# CPU-0.net
KiCad netlist of a schematic drawn in Altium Designer
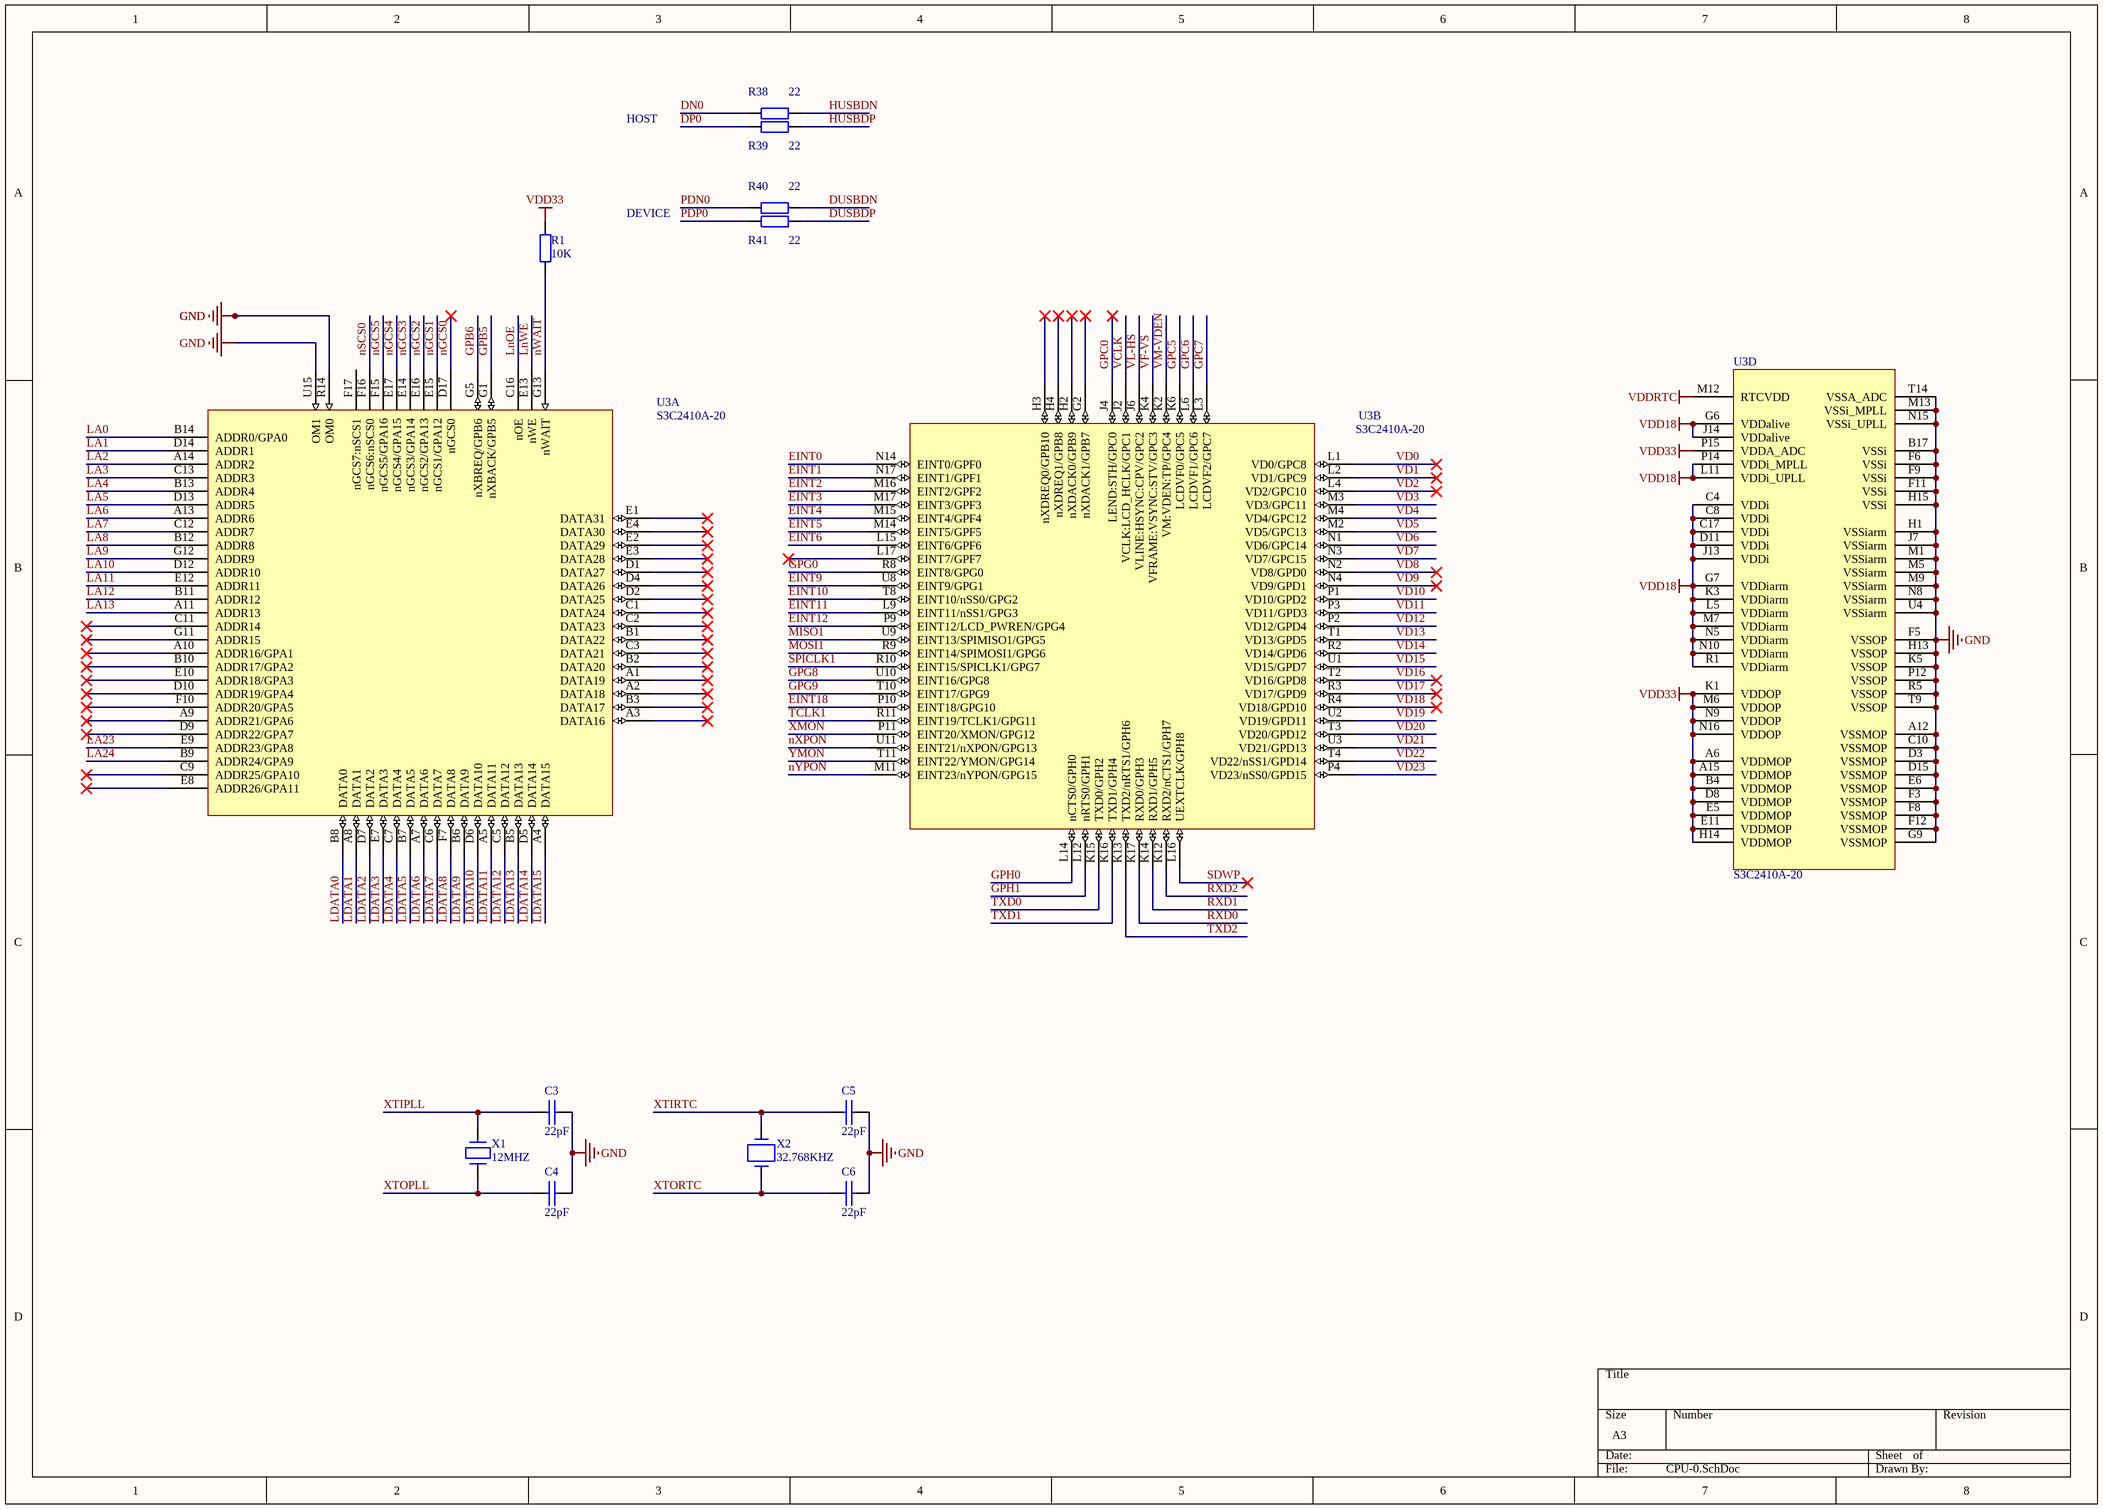
[diagram p0: CPU-0.SchDoc]

(export (version "E")
  (design (tool "Eeschema 10.0.6"))
  (components
    (comp (ref "C3")
      (value "22pF")
      (footprint "A型钽电容")
      (description "Capacitor")
      (libsource (lib "ARM_DEMO") (part "CAP_1"))
    )
    (comp (ref "C4")
      (value "22pF")
      (footprint "A型钽电容")
      (description "Capacitor")
      (libsource (lib "ARM_DEMO") (part "CAP_1"))
    )
    (comp (ref "C5")
      (value "22pF")
      (footprint "A型钽电容")
      (description "Capacitor")
      (libsource (lib "ARM_DEMO") (part "CAP_1"))
    )
    (comp (ref "C6")
      (value "22pF")
      (footprint "A型钽电容")
      (description "Capacitor")
      (libsource (lib "ARM_DEMO") (part "CAP_1"))
    )
    (comp (ref "R1")
      (value "10K")
      (footprint "0603R")
      (description "Resistor")
      (fields (field (name "Comment") "Res2") (field (name "PUBLISHER") "Altium Limited"))
      (libsource (lib "") (part "Res2_1_1"))
    )
    (comp (ref "R38")
      (value "22")
      (footprint "0603R")
      (description "Resistor")
      (fields (field (name "Comment") "Res2") (field (name "PUBLISHER") "Altium Limited"))
      (libsource (lib "ARM_DEMO") (part "Res2_1"))
    )
    (comp (ref "R39")
      (value "22")
      (footprint "0603R")
      (description "Resistor")
      (fields (field (name "Comment") "Res2") (field (name "PUBLISHER") "Altium Limited"))
      (libsource (lib "ARM_DEMO") (part "Res2_1"))
    )
    (comp (ref "R40")
      (value "22")
      (footprint "0603R")
      (description "Resistor")
      (fields (field (name "Comment") "Res2") (field (name "PUBLISHER") "Altium Limited"))
      (libsource (lib "ARM_DEMO") (part "Res2_1"))
    )
    (comp (ref "R41")
      (value "22")
      (footprint "0603R")
      (description "Resistor")
      (fields (field (name "Comment") "Res2") (field (name "PUBLISHER") "Altium Limited"))
      (libsource (lib "ARM_DEMO") (part "Res2_1"))
    )
    (comp (ref "U3")
      (value "S3C2410A-20")
      (footprint "FBGA272")
      (description "32-Bit RISC Microprocessor, 200 MHz, 1.8V (Core), 3.3V (Memory and IO), 272-Pin FBGA")
      (fields (field (name "PUBLISHER") "Altium Limited"))
      (libsource (lib "ARM_DEMO") (part "S3C2410A-20"))
    )
    (comp (ref "X1") (value "12MHZ") (footprint "OSC2PR-1") (libsource (lib "ARM_DEMO") (part "CRYSTAL")))
    (comp (ref "X2") (value "32.768KHZ") (footprint "XTAL-B") (libsource (lib "ARM_DEMO") (part "CRYSTAL_1")))
  )
  (nets
    (net (code "1") (name "/DN0") (class "Default")
      (node (ref "R38") (pin "1") (pinfunction "1_1") (pintype "passive"))
    )
    (net (code "2") (name "/DP0") (class "Default")
      (node (ref "R39") (pin "1") (pinfunction "1_1") (pintype "passive"))
    )
    (net (code "3") (name "/DUSBDN") (class "Default")
      (node (ref "R40") (pin "2") (pinfunction "2_2") (pintype "passive"))
    )
    (net (code "4") (name "/DUSBDP") (class "Default")
      (node (ref "R41") (pin "2") (pinfunction "2_2") (pintype "passive"))
    )
    (net (code "5") (name "/EINT0") (class "Default")
      (node (ref "U3") (pin "N14") (pinfunction "EINT0/GPF0_N14") (pintype "bidirectional"))
    )
    (net (code "6") (name "/EINT1") (class "Default")
      (node (ref "U3") (pin "N17") (pinfunction "EINT1/GPF1_N17") (pintype "bidirectional"))
    )
    (net (code "7") (name "/EINT2") (class "Default")
      (node (ref "U3") (pin "M16") (pinfunction "EINT2/GPF2_M16") (pintype "bidirectional"))
    )
    (net (code "8") (name "/EINT3") (class "Default")
      (node (ref "U3") (pin "M17") (pinfunction "EINT3/GPF3_M17") (pintype "bidirectional"))
    )
    (net (code "9") (name "/EINT4") (class "Default")
      (node (ref "U3") (pin "M15") (pinfunction "EINT4/GPF4_M15") (pintype "bidirectional"))
    )
    (net (code "10") (name "/EINT5") (class "Default")
      (node (ref "U3") (pin "M14") (pinfunction "EINT5/GPF5_M14") (pintype "bidirectional"))
    )
    (net (code "11") (name "/EINT6") (class "Default")
      (node (ref "U3") (pin "L15") (pinfunction "EINT6/GPF6_L15") (pintype "bidirectional"))
    )
    (net (code "12") (name "/EINT9") (class "Default")
      (node (ref "U3") (pin "U8") (pinfunction "EINT9/GPG1_U8") (pintype "bidirectional"))
    )
    (net (code "13") (name "/EINT10") (class "Default")
      (node (ref "U3") (pin "T8") (pinfunction "EINT10/nSS0/GPG2_T8") (pintype "bidirectional"))
    )
    (net (code "14") (name "/EINT11") (class "Default")
      (node (ref "U3") (pin "L9") (pinfunction "EINT11/nSS1/GPG3_L9") (pintype "bidirectional"))
    )
    (net (code "15") (name "/EINT12") (class "Default")
      (node (ref "U3") (pin "P9") (pinfunction "EINT12/LCD_PWREN/GPG4_P9") (pintype "bidirectional"))
    )
    (net (code "16") (name "/EINT18") (class "Default")
      (node (ref "U3") (pin "P10") (pinfunction "EINT18/GPG10_P10") (pintype "bidirectional"))
    )
    (net (code "17") (name "/GPB5") (class "Default")
      (node (ref "U3") (pin "G1") (pinfunction "nXBACK/GPB5_G1") (pintype "bidirectional"))
    )
    (net (code "18") (name "/GPB6") (class "Default")
      (node (ref "U3") (pin "G5") (pinfunction "nXBREQ/GPB6_G5") (pintype "bidirectional"))
    )
    (net (code "19") (name "/GPC0") (class "Default")
      (node (ref "U3") (pin "J4") (pinfunction "LEND:STH/GPC0_J4") (pintype "bidirectional+no_connect"))
    )
    (net (code "20") (name "/GPC5") (class "Default")
      (node (ref "U3") (pin "K6") (pinfunction "LCDVF0/GPC5_K6") (pintype "bidirectional"))
    )
    (net (code "21") (name "/GPC6") (class "Default")
      (node (ref "U3") (pin "L6") (pinfunction "LCDVF1/GPC6_L6") (pintype "bidirectional"))
    )
    (net (code "22") (name "/GPC7") (class "Default")
      (node (ref "U3") (pin "L3") (pinfunction "LCDVF2/GPC7_L3") (pintype "bidirectional"))
    )
    (net (code "23") (name "/GPG0") (class "Default")
      (node (ref "U3") (pin "R8") (pinfunction "EINT8/GPG0_R8") (pintype "bidirectional"))
    )
    (net (code "24") (name "/GPG8") (class "Default")
      (node (ref "U3") (pin "U10") (pinfunction "EINT16/GPG8_U10") (pintype "bidirectional"))
    )
    (net (code "25") (name "/GPG9") (class "Default")
      (node (ref "U3") (pin "T10") (pinfunction "EINT17/GPG9_T10") (pintype "bidirectional"))
    )
    (net (code "26") (name "/GPH0") (class "Default")
      (node (ref "U3") (pin "L14") (pinfunction "nCTS0/GPH0_L14") (pintype "bidirectional"))
    )
    (net (code "27") (name "/GPH1") (class "Default")
      (node (ref "U3") (pin "L12") (pinfunction "nRTS0/GPH1_L12") (pintype "bidirectional"))
    )
    (net (code "28") (name "/HUSBDN") (class "Default")
      (node (ref "R38") (pin "2") (pinfunction "2_2") (pintype "passive"))
    )
    (net (code "29") (name "/HUSBDP") (class "Default")
      (node (ref "R39") (pin "2") (pinfunction "2_2") (pintype "passive"))
    )
    (net (code "30") (name "/LA0") (class "Default")
      (node (ref "U3") (pin "B14") (pinfunction "ADDR0/GPA0_B14") (pintype "tri_state"))
    )
    (net (code "31") (name "/LA1") (class "Default")
      (node (ref "U3") (pin "D14") (pinfunction "ADDR1_D14") (pintype "tri_state"))
    )
    (net (code "32") (name "/LA2") (class "Default")
      (node (ref "U3") (pin "A14") (pinfunction "ADDR2_A14") (pintype "tri_state"))
    )
    (net (code "33") (name "/LA3") (class "Default")
      (node (ref "U3") (pin "C13") (pinfunction "ADDR3_C13") (pintype "tri_state"))
    )
    (net (code "34") (name "/LA4") (class "Default")
      (node (ref "U3") (pin "B13") (pinfunction "ADDR4_B13") (pintype "tri_state"))
    )
    (net (code "35") (name "/LA5") (class "Default")
      (node (ref "U3") (pin "D13") (pinfunction "ADDR5_D13") (pintype "tri_state"))
    )
    (net (code "36") (name "/LA6") (class "Default")
      (node (ref "U3") (pin "A13") (pinfunction "ADDR6_A13") (pintype "tri_state"))
    )
    (net (code "37") (name "/LA7") (class "Default")
      (node (ref "U3") (pin "C12") (pinfunction "ADDR7_C12") (pintype "tri_state"))
    )
    (net (code "38") (name "/LA8") (class "Default")
      (node (ref "U3") (pin "B12") (pinfunction "ADDR8_B12") (pintype "tri_state"))
    )
    (net (code "39") (name "/LA9") (class "Default")
      (node (ref "U3") (pin "G12") (pinfunction "ADDR9_G12") (pintype "tri_state"))
    )
    (net (code "40") (name "/LA10") (class "Default")
      (node (ref "U3") (pin "D12") (pinfunction "ADDR10_D12") (pintype "tri_state"))
    )
    (net (code "41") (name "/LA11") (class "Default")
      (node (ref "U3") (pin "E12") (pinfunction "ADDR11_E12") (pintype "tri_state"))
    )
    (net (code "42") (name "/LA12") (class "Default")
      (node (ref "U3") (pin "B11") (pinfunction "ADDR12_B11") (pintype "tri_state"))
    )
    (net (code "43") (name "/LA13") (class "Default")
      (node (ref "U3") (pin "A11") (pinfunction "ADDR13_A11") (pintype "tri_state"))
    )
    (net (code "44") (name "/LA23") (class "Default")
      (node (ref "U3") (pin "E9") (pinfunction "ADDR23/GPA8_E9") (pintype "tri_state"))
    )
    (net (code "45") (name "/LA24") (class "Default")
      (node (ref "U3") (pin "B9") (pinfunction "ADDR24/GPA9_B9") (pintype "tri_state"))
    )
    (net (code "46") (name "/LDATA0") (class "Default")
      (node (ref "U3") (pin "B8") (pinfunction "DATA0_B8") (pintype "bidirectional"))
    )
    (net (code "47") (name "/LDATA1") (class "Default")
      (node (ref "U3") (pin "A8") (pinfunction "DATA1_A8") (pintype "bidirectional"))
    )
    (net (code "48") (name "/LDATA2") (class "Default")
      (node (ref "U3") (pin "D7") (pinfunction "DATA2_D7") (pintype "bidirectional"))
    )
    (net (code "49") (name "/LDATA3") (class "Default")
      (node (ref "U3") (pin "E7") (pinfunction "DATA3_E7") (pintype "bidirectional"))
    )
    (net (code "50") (name "/LDATA4") (class "Default")
      (node (ref "U3") (pin "C7") (pinfunction "DATA4_C7") (pintype "bidirectional"))
    )
    (net (code "51") (name "/LDATA5") (class "Default")
      (node (ref "U3") (pin "B7") (pinfunction "DATA5_B7") (pintype "bidirectional"))
    )
    (net (code "52") (name "/LDATA6") (class "Default")
      (node (ref "U3") (pin "A7") (pinfunction "DATA6_A7") (pintype "bidirectional"))
    )
    (net (code "53") (name "/LDATA7") (class "Default")
      (node (ref "U3") (pin "C6") (pinfunction "DATA7_C6") (pintype "bidirectional"))
    )
    (net (code "54") (name "/LDATA8") (class "Default")
      (node (ref "U3") (pin "F7") (pinfunction "DATA8_F7") (pintype "bidirectional"))
    )
    (net (code "55") (name "/LDATA9") (class "Default")
      (node (ref "U3") (pin "B6") (pinfunction "DATA9_B6") (pintype "bidirectional"))
    )
    (net (code "56") (name "/LDATA10") (class "Default")
      (node (ref "U3") (pin "D6") (pinfunction "DATA10_D6") (pintype "bidirectional"))
    )
    (net (code "57") (name "/LDATA11") (class "Default")
      (node (ref "U3") (pin "A5") (pinfunction "DATA11_A5") (pintype "bidirectional"))
    )
    (net (code "58") (name "/LDATA12") (class "Default")
      (node (ref "U3") (pin "C5") (pinfunction "DATA12_C5") (pintype "bidirectional"))
    )
    (net (code "59") (name "/LDATA13") (class "Default")
      (node (ref "U3") (pin "B5") (pinfunction "DATA13_B5") (pintype "bidirectional"))
    )
    (net (code "60") (name "/LDATA14") (class "Default")
      (node (ref "U3") (pin "D5") (pinfunction "DATA14_D5") (pintype "bidirectional"))
    )
    (net (code "61") (name "/LDATA15") (class "Default")
      (node (ref "U3") (pin "A4") (pinfunction "DATA15_A4") (pintype "bidirectional"))
    )
    (net (code "62") (name "/LnOE") (class "Default")
      (node (ref "U3") (pin "C16") (pinfunction "nOE_C16") (pintype "tri_state"))
    )
    (net (code "63") (name "/LnWE") (class "Default")
      (node (ref "U3") (pin "E13") (pinfunction "nWE_E13") (pintype "tri_state"))
    )
    (net (code "64") (name "/MISO1") (class "Default")
      (node (ref "U3") (pin "U9") (pinfunction "EINT13/SPIMISO1/GPG5_U9") (pintype "bidirectional"))
    )
    (net (code "65") (name "/MOSI1") (class "Default")
      (node (ref "U3") (pin "R9") (pinfunction "EINT14/SPIMOSI1/GPG6_R9") (pintype "bidirectional"))
    )
    (net (code "66") (name "/PDN0") (class "Default")
      (node (ref "R40") (pin "1") (pinfunction "1_1") (pintype "passive"))
    )
    (net (code "67") (name "/PDP0") (class "Default")
      (node (ref "R41") (pin "1") (pinfunction "1_1") (pintype "passive"))
    )
    (net (code "68") (name "/RXD0") (class "Default")
      (node (ref "U3") (pin "K17") (pinfunction "RXD0/GPH3_K17") (pintype "bidirectional"))
    )
    (net (code "69") (name "/RXD1") (class "Default")
      (node (ref "U3") (pin "K14") (pinfunction "RXD1/GPH5_K14") (pintype "bidirectional"))
    )
    (net (code "70") (name "/RXD2") (class "Default")
      (node (ref "U3") (pin "K12") (pinfunction "RXD2/nCTS1/GPH7_K12") (pintype "bidirectional"))
    )
    (net (code "71") (name "/SDWP") (class "Default")
      (node (ref "U3") (pin "L16") (pinfunction "UEXTCLK/GPH8_L16") (pintype "bidirectional+no_connect"))
    )
    (net (code "72") (name "/SPICLK1") (class "Default")
      (node (ref "U3") (pin "R10") (pinfunction "EINT15/SPICLK1/GPG7_R10") (pintype "bidirectional"))
    )
    (net (code "73") (name "/TCLK1") (class "Default")
      (node (ref "U3") (pin "R11") (pinfunction "EINT19/TCLK1/GPG11_R11") (pintype "bidirectional"))
    )
    (net (code "74") (name "/TXD0") (class "Default")
      (node (ref "U3") (pin "K15") (pinfunction "TXD0/GPH2_K15") (pintype "bidirectional"))
    )
    (net (code "75") (name "/TXD1") (class "Default")
      (node (ref "U3") (pin "K16") (pinfunction "TXD1/GPH4_K16") (pintype "bidirectional"))
    )
    (net (code "76") (name "/TXD2") (class "Default")
      (node (ref "U3") (pin "K13") (pinfunction "TXD2/nRTS1/GPH6_K13") (pintype "bidirectional"))
    )
    (net (code "77") (name "/VCLK") (class "Default")
      (node (ref "U3") (pin "J2") (pinfunction "VCLK:LCD_HCLK/GPC1_J2") (pintype "bidirectional"))
    )
    (net (code "78") (name "/VD0") (class "Default")
      (node (ref "U3") (pin "L1") (pinfunction "VD0/GPC8_L1") (pintype "bidirectional+no_connect"))
    )
    (net (code "79") (name "/VD1") (class "Default")
      (node (ref "U3") (pin "L2") (pinfunction "VD1/GPC9_L2") (pintype "bidirectional+no_connect"))
    )
    (net (code "80") (name "/VD2") (class "Default")
      (node (ref "U3") (pin "L4") (pinfunction "VD2/GPC10_L4") (pintype "bidirectional+no_connect"))
    )
    (net (code "81") (name "/VD3") (class "Default")
      (node (ref "U3") (pin "M3") (pinfunction "VD3/GPC11_M3") (pintype "bidirectional"))
    )
    (net (code "82") (name "/VD4") (class "Default")
      (node (ref "U3") (pin "M4") (pinfunction "VD4/GPC12_M4") (pintype "bidirectional"))
    )
    (net (code "83") (name "/VD5") (class "Default")
      (node (ref "U3") (pin "M2") (pinfunction "VD5/GPC13_M2") (pintype "bidirectional"))
    )
    (net (code "84") (name "/VD6") (class "Default")
      (node (ref "U3") (pin "N1") (pinfunction "VD6/GPC14_N1") (pintype "bidirectional"))
    )
    (net (code "85") (name "/VD7") (class "Default")
      (node (ref "U3") (pin "N3") (pinfunction "VD7/GPC15_N3") (pintype "bidirectional"))
    )
    (net (code "86") (name "/VD8") (class "Default")
      (node (ref "U3") (pin "N2") (pinfunction "VD8/GPD0_N2") (pintype "bidirectional+no_connect"))
    )
    (net (code "87") (name "/VD9") (class "Default")
      (node (ref "U3") (pin "N4") (pinfunction "VD9/GPD1_N4") (pintype "bidirectional+no_connect"))
    )
    (net (code "88") (name "/VD10") (class "Default")
      (node (ref "U3") (pin "P1") (pinfunction "VD10/GPD2_P1") (pintype "bidirectional"))
    )
    (net (code "89") (name "/VD11") (class "Default")
      (node (ref "U3") (pin "P3") (pinfunction "VD11/GPD3_P3") (pintype "bidirectional"))
    )
    (net (code "90") (name "/VD12") (class "Default")
      (node (ref "U3") (pin "P2") (pinfunction "VD12/GPD4_P2") (pintype "bidirectional"))
    )
    (net (code "91") (name "/VD13") (class "Default")
      (node (ref "U3") (pin "T1") (pinfunction "VD13/GPD5_T1") (pintype "bidirectional"))
    )
    (net (code "92") (name "/VD14") (class "Default")
      (node (ref "U3") (pin "R2") (pinfunction "VD14/GPD6_R2") (pintype "bidirectional"))
    )
    (net (code "93") (name "/VD15") (class "Default")
      (node (ref "U3") (pin "U1") (pinfunction "VD15/GPD7_U1") (pintype "bidirectional"))
    )
    (net (code "94") (name "/VD16") (class "Default")
      (node (ref "U3") (pin "T2") (pinfunction "VD16/GPD8_T2") (pintype "bidirectional+no_connect"))
    )
    (net (code "95") (name "/VD17") (class "Default")
      (node (ref "U3") (pin "R3") (pinfunction "VD17/GPD9_R3") (pintype "bidirectional+no_connect"))
    )
    (net (code "96") (name "/VD18") (class "Default")
      (node (ref "U3") (pin "R4") (pinfunction "VD18/GPD10_R4") (pintype "bidirectional+no_connect"))
    )
    (net (code "97") (name "/VD19") (class "Default")
      (node (ref "U3") (pin "U2") (pinfunction "VD19/GPD11_U2") (pintype "bidirectional"))
    )
    (net (code "98") (name "/VD20") (class "Default")
      (node (ref "U3") (pin "T3") (pinfunction "VD20/GPD12_T3") (pintype "bidirectional"))
    )
    (net (code "99") (name "/VD21") (class "Default")
      (node (ref "U3") (pin "U3") (pinfunction "VD21/GPD13_U3") (pintype "bidirectional"))
    )
    (net (code "100") (name "/VD22") (class "Default")
      (node (ref "U3") (pin "T4") (pinfunction "VD22/nSS1/GPD14_T4") (pintype "bidirectional"))
    )
    (net (code "101") (name "/VD23") (class "Default")
      (node (ref "U3") (pin "P4") (pinfunction "VD23/nSS0/GPD15_P4") (pintype "bidirectional"))
    )
    (net (code "102") (name "/VF-VS") (class "Default")
      (node (ref "U3") (pin "K4") (pinfunction "VFRAME:VSYNC:STV/GPC3_K4") (pintype "bidirectional"))
    )
    (net (code "103") (name "/VL-HS") (class "Default")
      (node (ref "U3") (pin "J6") (pinfunction "VLINE:HSYNC:CPV/GPC2_J6") (pintype "bidirectional"))
    )
    (net (code "104") (name "/VM-VDEN") (class "Default")
      (node (ref "U3") (pin "K2") (pinfunction "VM:VDEN:TP/GPC4_K2") (pintype "bidirectional"))
    )
    (net (code "105") (name "/XMON") (class "Default")
      (node (ref "U3") (pin "P11") (pinfunction "EINT20/XMON/GPG12_P11") (pintype "bidirectional"))
    )
    (net (code "106") (name "/XTIPLL") (class "Default")
      (node (ref "C3") (pin "1") (pinfunction "1_1") (pintype "passive"))
      (node (ref "X1") (pin "2") (pintype "passive"))
    )
    (net (code "107") (name "/XTIRTC") (class "Default")
      (node (ref "C5") (pin "1") (pinfunction "1_1") (pintype "passive"))
      (node (ref "X2") (pin "2") (pinfunction "2_2") (pintype "passive"))
    )
    (net (code "108") (name "/XTOPLL") (class "Default")
      (node (ref "C4") (pin "1") (pinfunction "1_1") (pintype "passive"))
      (node (ref "X1") (pin "1") (pintype "passive"))
    )
    (net (code "109") (name "/XTORTC") (class "Default")
      (node (ref "C6") (pin "1") (pinfunction "1_1") (pintype "passive"))
      (node (ref "X2") (pin "1") (pinfunction "1_1") (pintype "passive"))
    )
    (net (code "110") (name "/YMON") (class "Default")
      (node (ref "U3") (pin "T11") (pinfunction "EINT22/YMON/GPG14_T11") (pintype "bidirectional"))
    )
    (net (code "111") (name "/nGCS0") (class "Default")
      (node (ref "U3") (pin "D17") (pinfunction "nGCS0_D17") (pintype "tri_state+no_connect"))
    )
    (net (code "112") (name "/nGCS1") (class "Default")
      (node (ref "U3") (pin "E15") (pinfunction "nGCS1/GPA12_E15") (pintype "tri_state"))
    )
    (net (code "113") (name "/nGCS2") (class "Default")
      (node (ref "U3") (pin "E16") (pinfunction "nGCS2/GPA13_E16") (pintype "tri_state"))
    )
    (net (code "114") (name "/nGCS3") (class "Default")
      (node (ref "U3") (pin "E14") (pinfunction "nGCS3/GPA14_E14") (pintype "tri_state"))
    )
    (net (code "115") (name "/nGCS4") (class "Default")
      (node (ref "U3") (pin "E17") (pinfunction "nGCS4/GPA15_E17") (pintype "tri_state"))
    )
    (net (code "116") (name "/nGCS5") (class "Default")
      (node (ref "U3") (pin "F15") (pinfunction "nGCS5/GPA16_F15") (pintype "tri_state"))
    )
    (net (code "117") (name "/nSCS0") (class "Default")
      (node (ref "U3") (pin "F16") (pinfunction "nGCS6:nSCS0_F16") (pintype "tri_state"))
    )
    (net (code "118") (name "/nWAIT") (class "Default")
      (node (ref "R1") (pin "1") (pinfunction "1_1") (pintype "passive"))
      (node (ref "U3") (pin "G13") (pinfunction "nWAIT_G13") (pintype "input"))
    )
    (net (code "119") (name "/nXPON") (class "Default")
      (node (ref "U3") (pin "U11") (pinfunction "EINT21/nXPON/GPG13_U11") (pintype "bidirectional"))
    )
    (net (code "120") (name "/nYPON") (class "Default")
      (node (ref "U3") (pin "M11") (pinfunction "EINT23/nYPON/GPG15_M11") (pintype "bidirectional"))
    )
    (net (code "121") (name "GND") (class "Default")
      (node (ref "C3") (pin "2") (pinfunction "2_2") (pintype "passive"))
      (node (ref "C4") (pin "2") (pinfunction "2_2") (pintype "passive"))
      (node (ref "C5") (pin "2") (pinfunction "2_2") (pintype "passive"))
      (node (ref "C6") (pin "2") (pinfunction "2_2") (pintype "passive"))
      (node (ref "U3") (pin "A12") (pinfunction "VSSMOP_A12") (pintype "power_in"))
      (node (ref "U3") (pin "B17") (pinfunction "VSSi_B17") (pintype "power_in"))
      (node (ref "U3") (pin "C10") (pinfunction "VSSMOP_C10") (pintype "power_in"))
      (node (ref "U3") (pin "D15") (pinfunction "VSSMOP_D15") (pintype "power_in"))
      (node (ref "U3") (pin "D3") (pinfunction "VSSMOP_D3") (pintype "power_in"))
      (node (ref "U3") (pin "E6") (pinfunction "VSSMOP_E6") (pintype "power_in"))
      (node (ref "U3") (pin "F11") (pinfunction "VSSi_F11") (pintype "power_in"))
      (node (ref "U3") (pin "F12") (pinfunction "VSSMOP_F12") (pintype "power_in"))
      (node (ref "U3") (pin "F3") (pinfunction "VSSMOP_F3") (pintype "power_in"))
      (node (ref "U3") (pin "F5") (pinfunction "VSSOP_F5") (pintype "power_in"))
      (node (ref "U3") (pin "F6") (pinfunction "VSSi_F6") (pintype "power_in"))
      (node (ref "U3") (pin "F8") (pinfunction "VSSMOP_F8") (pintype "power_in"))
      (node (ref "U3") (pin "F9") (pinfunction "VSSi_F9") (pintype "power_in"))
      (node (ref "U3") (pin "G9") (pinfunction "VSSMOP_G9") (pintype "power_in"))
      (node (ref "U3") (pin "H1") (pinfunction "VSSiarm_H1") (pintype "power_in"))
      (node (ref "U3") (pin "H13") (pinfunction "VSSOP_H13") (pintype "power_in"))
      (node (ref "U3") (pin "H15") (pinfunction "VSSi_H15") (pintype "power_in"))
      (node (ref "U3") (pin "J7") (pinfunction "VSSiarm_J7") (pintype "power_in"))
      (node (ref "U3") (pin "K5") (pinfunction "VSSOP_K5") (pintype "power_in"))
      (node (ref "U3") (pin "M1") (pinfunction "VSSiarm_M1") (pintype "power_in"))
      (node (ref "U3") (pin "M13") (pinfunction "VSSi_MPLL_M13") (pintype "power_in"))
      (node (ref "U3") (pin "M5") (pinfunction "VSSiarm_M5") (pintype "power_in"))
      (node (ref "U3") (pin "M9") (pinfunction "VSSiarm_M9") (pintype "power_in"))
      (node (ref "U3") (pin "N15") (pinfunction "VSSi_UPLL_N15") (pintype "power_in"))
      (node (ref "U3") (pin "N8") (pinfunction "VSSiarm_N8") (pintype "power_in"))
      (node (ref "U3") (pin "P12") (pinfunction "VSSOP_P12") (pintype "power_in"))
      (node (ref "U3") (pin "R14") (pinfunction "OM0_R14") (pintype "input"))
      (node (ref "U3") (pin "R5") (pinfunction "VSSOP_R5") (pintype "power_in"))
      (node (ref "U3") (pin "T14") (pinfunction "VSSA_ADC_T14") (pintype "power_in"))
      (node (ref "U3") (pin "T9") (pinfunction "VSSOP_T9") (pintype "power_in"))
      (node (ref "U3") (pin "U15") (pinfunction "OM1_U15") (pintype "input"))
      (node (ref "U3") (pin "U4") (pinfunction "VSSiarm_U4") (pintype "power_in"))
    )
    (net (code "122") (name "VDD18") (class "Default")
      (node (ref "U3") (pin "C17") (pinfunction "VDDi_C17") (pintype "power_in"))
      (node (ref "U3") (pin "C4") (pinfunction "VDDi_C4") (pintype "power_in"))
      (node (ref "U3") (pin "C8") (pinfunction "VDDi_C8") (pintype "power_in"))
      (node (ref "U3") (pin "D11") (pinfunction "VDDi_D11") (pintype "power_in"))
      (node (ref "U3") (pin "G6") (pinfunction "VDDalive_G6") (pintype "power_in"))
      (node (ref "U3") (pin "G7") (pinfunction "VDDiarm_G7") (pintype "power_in"))
      (node (ref "U3") (pin "J13") (pinfunction "VDDi_J13") (pintype "power_in"))
      (node (ref "U3") (pin "J14") (pinfunction "VDDalive_J14") (pintype "power_in"))
      (node (ref "U3") (pin "K3") (pinfunction "VDDiarm_K3") (pintype "power_in"))
      (node (ref "U3") (pin "L11") (pinfunction "VDDi_UPLL_L11") (pintype "power_in"))
      (node (ref "U3") (pin "L5") (pinfunction "VDDiarm_L5") (pintype "power_in"))
      (node (ref "U3") (pin "M7") (pinfunction "VDDiarm_M7") (pintype "power_in"))
      (node (ref "U3") (pin "N10") (pinfunction "VDDiarm_N10") (pintype "power_in"))
      (node (ref "U3") (pin "N5") (pinfunction "VDDiarm_N5") (pintype "power_in"))
      (node (ref "U3") (pin "P14") (pinfunction "VDDi_MPLL_P14") (pintype "power_in"))
      (node (ref "U3") (pin "R1") (pinfunction "VDDiarm_R1") (pintype "power_in"))
    )
    (net (code "123") (name "VDD33") (class "Default")
      (node (ref "R1") (pin "2") (pinfunction "2_2") (pintype "passive"))
      (node (ref "U3") (pin "A15") (pinfunction "VDDMOP_A15") (pintype "power_in"))
      (node (ref "U3") (pin "A6") (pinfunction "VDDMOP_A6") (pintype "power_in"))
      (node (ref "U3") (pin "B4") (pinfunction "VDDMOP_B4") (pintype "power_in"))
      (node (ref "U3") (pin "D8") (pinfunction "VDDMOP_D8") (pintype "power_in"))
      (node (ref "U3") (pin "E11") (pinfunction "VDDMOP_E11") (pintype "power_in"))
      (node (ref "U3") (pin "E5") (pinfunction "VDDMOP_E5") (pintype "power_in"))
      (node (ref "U3") (pin "H14") (pinfunction "VDDMOP_H14") (pintype "power_in"))
      (node (ref "U3") (pin "K1") (pinfunction "VDDOP_K1") (pintype "power_in"))
      (node (ref "U3") (pin "M6") (pinfunction "VDDOP_M6") (pintype "power_in"))
      (node (ref "U3") (pin "N16") (pinfunction "VDDOP_N16") (pintype "power_in"))
      (node (ref "U3") (pin "N9") (pinfunction "VDDOP_N9") (pintype "power_in"))
      (node (ref "U3") (pin "P15") (pinfunction "VDDA_ADC_P15") (pintype "power_in"))
    )
    (net (code "124") (name "VDDRTC") (class "Default")
      (node (ref "U3") (pin "M12") (pinfunction "RTCVDD_M12") (pintype "power_in"))
    )
    (net (code "125") (name "unconnected-(U3A-ADDR14-PadC11)") (class "Default")
      (node (ref "U3") (pin "C11") (pinfunction "ADDR14_C11") (pintype "tri_state+no_connect"))
    )
    (net (code "126") (name "unconnected-(U3A-ADDR15-PadG11)") (class "Default")
      (node (ref "U3") (pin "G11") (pinfunction "ADDR15_G11") (pintype "tri_state+no_connect"))
    )
    (net (code "127") (name "unconnected-(U3A-ADDR16{slash}GPA1-PadA10)") (class "Default")
      (node (ref "U3") (pin "A10") (pinfunction "ADDR16/GPA1_A10") (pintype "tri_state+no_connect"))
    )
    (net (code "128") (name "unconnected-(U3A-ADDR17{slash}GPA2-PadB10)") (class "Default")
      (node (ref "U3") (pin "B10") (pinfunction "ADDR17/GPA2_B10") (pintype "tri_state+no_connect"))
    )
    (net (code "129") (name "unconnected-(U3A-ADDR18{slash}GPA3-PadE10)") (class "Default")
      (node (ref "U3") (pin "E10") (pinfunction "ADDR18/GPA3_E10") (pintype "tri_state+no_connect"))
    )
    (net (code "130") (name "unconnected-(U3A-ADDR19{slash}GPA4-PadD10)") (class "Default")
      (node (ref "U3") (pin "D10") (pinfunction "ADDR19/GPA4_D10") (pintype "tri_state+no_connect"))
    )
    (net (code "131") (name "unconnected-(U3A-ADDR20{slash}GPA5-PadF10)") (class "Default")
      (node (ref "U3") (pin "F10") (pinfunction "ADDR20/GPA5_F10") (pintype "tri_state+no_connect"))
    )
    (net (code "132") (name "unconnected-(U3A-ADDR21{slash}GPA6-PadA9)") (class "Default")
      (node (ref "U3") (pin "A9") (pinfunction "ADDR21/GPA6_A9") (pintype "tri_state+no_connect"))
    )
    (net (code "133") (name "unconnected-(U3A-ADDR22{slash}GPA7-PadD9)") (class "Default")
      (node (ref "U3") (pin "D9") (pinfunction "ADDR22/GPA7_D9") (pintype "tri_state+no_connect"))
    )
    (net (code "134") (name "unconnected-(U3A-ADDR25{slash}GPA10-PadC9)") (class "Default")
      (node (ref "U3") (pin "C9") (pinfunction "ADDR25/GPA10_C9") (pintype "tri_state+no_connect"))
    )
    (net (code "135") (name "unconnected-(U3A-ADDR26{slash}GPA11-PadE8)") (class "Default")
      (node (ref "U3") (pin "E8") (pinfunction "ADDR26/GPA11_E8") (pintype "tri_state+no_connect"))
    )
    (net (code "136") (name "unconnected-(U3A-DATA16-PadA3)") (class "Default")
      (node (ref "U3") (pin "A3") (pinfunction "DATA16_A3") (pintype "bidirectional+no_connect"))
    )
    (net (code "137") (name "unconnected-(U3A-DATA17-PadB3)") (class "Default")
      (node (ref "U3") (pin "B3") (pinfunction "DATA17_B3") (pintype "bidirectional+no_connect"))
    )
    (net (code "138") (name "unconnected-(U3A-DATA18-PadA2)") (class "Default")
      (node (ref "U3") (pin "A2") (pinfunction "DATA18_A2") (pintype "bidirectional+no_connect"))
    )
    (net (code "139") (name "unconnected-(U3A-DATA19-PadA1)") (class "Default")
      (node (ref "U3") (pin "A1") (pinfunction "DATA19_A1") (pintype "bidirectional+no_connect"))
    )
    (net (code "140") (name "unconnected-(U3A-DATA20-PadB2)") (class "Default")
      (node (ref "U3") (pin "B2") (pinfunction "DATA20_B2") (pintype "bidirectional+no_connect"))
    )
    (net (code "141") (name "unconnected-(U3A-DATA21-PadC3)") (class "Default")
      (node (ref "U3") (pin "C3") (pinfunction "DATA21_C3") (pintype "bidirectional+no_connect"))
    )
    (net (code "142") (name "unconnected-(U3A-DATA22-PadB1)") (class "Default")
      (node (ref "U3") (pin "B1") (pinfunction "DATA22_B1") (pintype "bidirectional+no_connect"))
    )
    (net (code "143") (name "unconnected-(U3A-DATA23-PadC2)") (class "Default")
      (node (ref "U3") (pin "C2") (pinfunction "DATA23_C2") (pintype "bidirectional+no_connect"))
    )
    (net (code "144") (name "unconnected-(U3A-DATA24-PadC1)") (class "Default")
      (node (ref "U3") (pin "C1") (pinfunction "DATA24_C1") (pintype "bidirectional+no_connect"))
    )
    (net (code "145") (name "unconnected-(U3A-DATA25-PadD2)") (class "Default")
      (node (ref "U3") (pin "D2") (pinfunction "DATA25_D2") (pintype "bidirectional+no_connect"))
    )
    (net (code "146") (name "unconnected-(U3A-DATA26-PadD4)") (class "Default")
      (node (ref "U3") (pin "D4") (pinfunction "DATA26_D4") (pintype "bidirectional+no_connect"))
    )
    (net (code "147") (name "unconnected-(U3A-DATA27-PadD1)") (class "Default")
      (node (ref "U3") (pin "D1") (pinfunction "DATA27_D1") (pintype "bidirectional+no_connect"))
    )
    (net (code "148") (name "unconnected-(U3A-DATA28-PadE3)") (class "Default")
      (node (ref "U3") (pin "E3") (pinfunction "DATA28_E3") (pintype "bidirectional+no_connect"))
    )
    (net (code "149") (name "unconnected-(U3A-DATA29-PadE2)") (class "Default")
      (node (ref "U3") (pin "E2") (pinfunction "DATA29_E2") (pintype "bidirectional+no_connect"))
    )
    (net (code "150") (name "unconnected-(U3A-DATA30-PadE4)") (class "Default")
      (node (ref "U3") (pin "E4") (pinfunction "DATA30_E4") (pintype "bidirectional+no_connect"))
    )
    (net (code "151") (name "unconnected-(U3A-DATA31-PadE1)") (class "Default")
      (node (ref "U3") (pin "E1") (pinfunction "DATA31_E1") (pintype "bidirectional+no_connect"))
    )
    (net (code "152") (name "unconnected-(U3A-nGCS7:nSCS1-PadF17)") (class "Default")
      (node (ref "U3") (pin "F17") (pinfunction "nGCS7:nSCS1_F17") (pintype "tri_state"))
    )
    (net (code "153") (name "unconnected-(U3B-EINT7{slash}GPF7-PadL17)") (class "Default")
      (node (ref "U3") (pin "L17") (pinfunction "EINT7/GPF7_L17") (pintype "bidirectional+no_connect"))
    )
    (net (code "154") (name "unconnected-(U3B-nXDACK0{slash}GPB9-PadH2)") (class "Default")
      (node (ref "U3") (pin "H2") (pinfunction "nXDACK0/GPB9_H2") (pintype "bidirectional+no_connect"))
    )
    (net (code "155") (name "unconnected-(U3B-nXDACK1{slash}GPB7-PadG2)") (class "Default")
      (node (ref "U3") (pin "G2") (pinfunction "nXDACK1/GPB7_G2") (pintype "bidirectional+no_connect"))
    )
    (net (code "156") (name "unconnected-(U3B-nXDREQ0{slash}GPB10-PadH3)") (class "Default")
      (node (ref "U3") (pin "H3") (pinfunction "nXDREQ0/GPB10_H3") (pintype "bidirectional+no_connect"))
    )
    (net (code "157") (name "unconnected-(U3B-nXDREQ1{slash}GPB8-PadH4)") (class "Default")
      (node (ref "U3") (pin "H4") (pinfunction "nXDREQ1/GPB8_H4") (pintype "bidirectional+no_connect"))
    )
  )
)
